# AD9364_Interface.net
KiCad netlist of a schematic drawn in Altium Designer
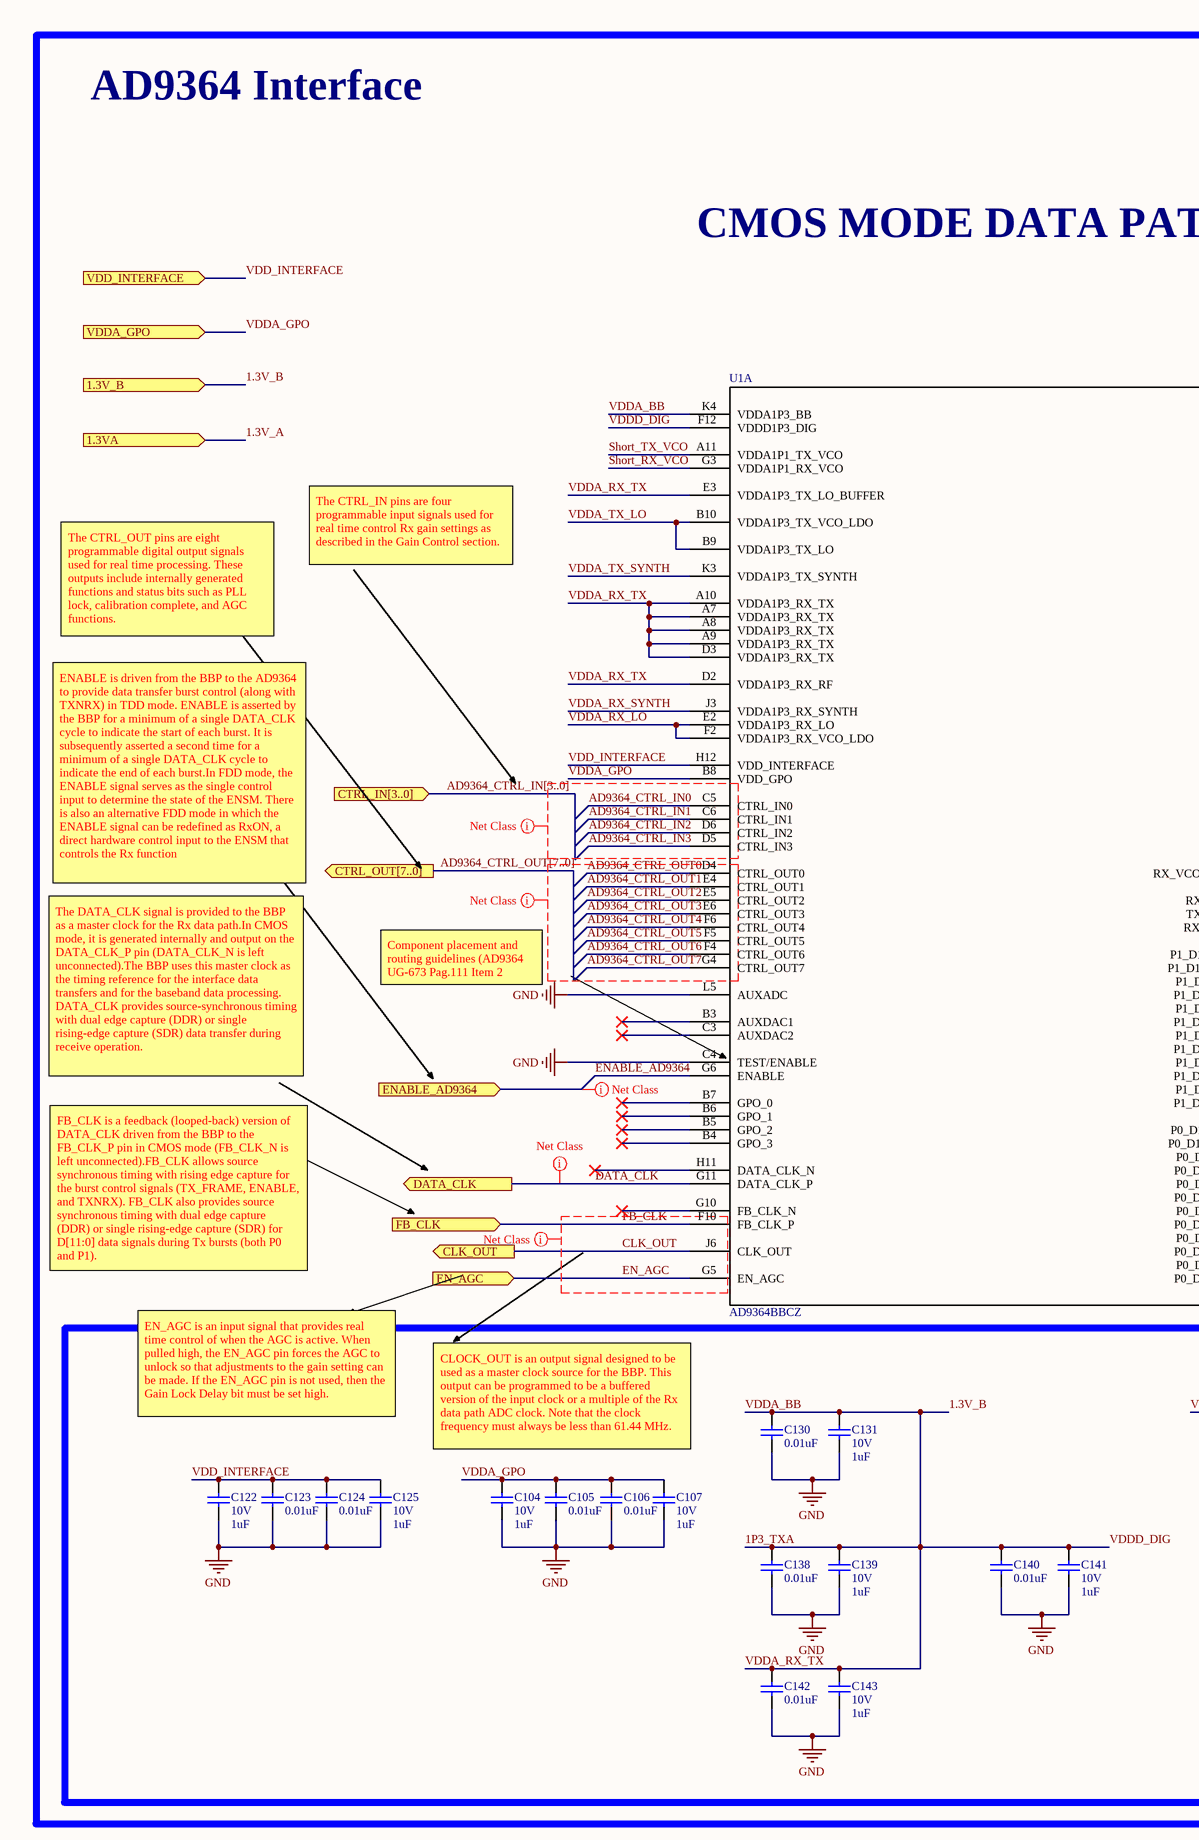
[diagram p0: AD9364_Interface.SchDoc, left]
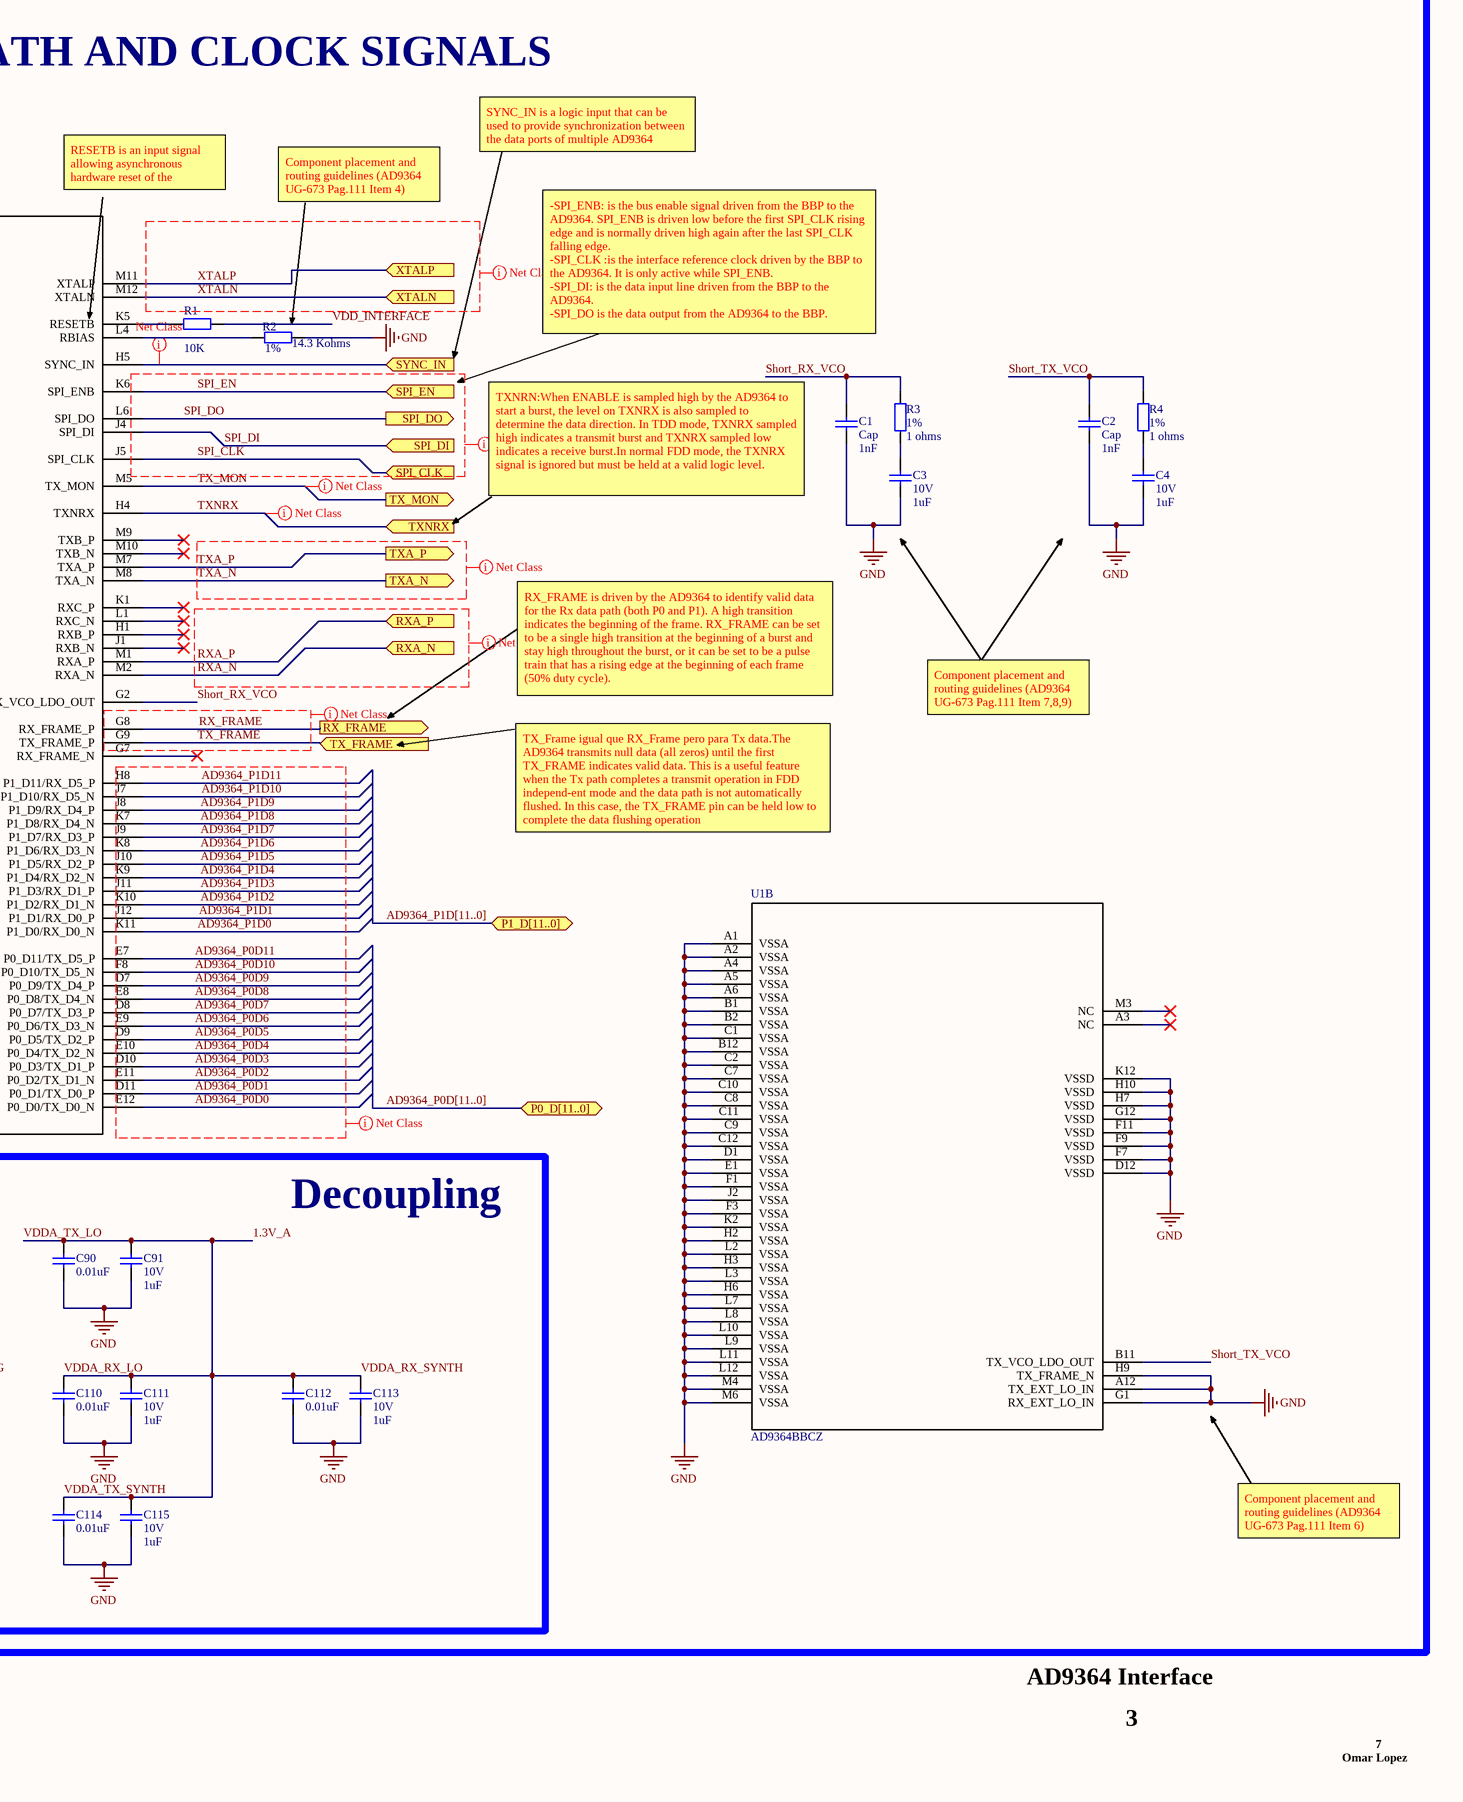
[diagram p1: AD9364_Interface.SchDoc, right]

(export (version "E")
  (design (tool "Eeschema 10.0.6"))
  (components
    (comp (ref "C1")
      (value "Cap")
      (footprint "MurataCapacitor:GRM0402MurataCap")
      (description "Capacitor")
      (fields
        (field (name "ALTIUM_VALUE") "1nF")
        (field (name "MANUFACTURER") "Murata")
        (field (name "TOLERANCE") "10%")
      )
      (libsource (lib "Miscellaneous Devices") (part "Cap"))
    )
    (comp (ref "C2")
      (value "Cap")
      (footprint "MurataCapacitor:GRM0402MurataCap")
      (description "Capacitor")
      (fields
        (field (name "ALTIUM_VALUE") "1nF")
        (field (name "MANUFACTURER") "Murata")
        (field (name "TOLERANCE") "10%")
      )
      (libsource (lib "Miscellaneous Devices") (part "Cap"))
    )
    (comp (ref "C3")
      (value "10V")
      (footprint "MurataCapacitor:GRM0402MurataCap")
      (description "Capacitor")
      (fields
        (field (name "ALTIUM_VALUE") "1uF")
        (field (name "MANUFACTURER") "Murata")
        (field (name "TOLERANCE") "10%")
      )
      (libsource (lib "Miscellaneous Devices") (part "Cap"))
    )
    (comp (ref "C4")
      (value "10V")
      (footprint "MurataCapacitor:GRM0402MurataCap")
      (description "Capacitor")
      (fields
        (field (name "ALTIUM_VALUE") "1uF")
        (field (name "MANUFACTURER") "Murata")
        (field (name "TOLERANCE") "10%")
      )
      (libsource (lib "Miscellaneous Devices") (part "Cap"))
    )
    (comp (ref "C90")
      (value "0.01uF")
      (footprint "MurataCapacitor:GRM0402MurataCap")
      (description "Capacitor")
      (fields (field (name "MANUFACTURER") "Murata") (field (name "TOLERANCE") "10%"))
      (libsource (lib "Miscellaneous Devices") (part "Cap"))
    )
    (comp (ref "C91")
      (value "10V")
      (footprint "MurataCapacitor:GRM0402MurataCap")
      (description "Capacitor")
      (fields
        (field (name "ALTIUM_VALUE") "1uF")
        (field (name "MANUFACTURER") "Murata")
        (field (name "TOLERANCE") "10%")
      )
      (libsource (lib "Miscellaneous Devices") (part "Cap"))
    )
    (comp (ref "C104")
      (value "10V")
      (footprint "MurataCapacitor:GRM0402MurataCap")
      (description "Capacitor")
      (fields
        (field (name "ALTIUM_VALUE") "1uF")
        (field (name "MANUFACTURER") "Murata")
        (field (name "TOLERANCE") "10%")
      )
      (libsource (lib "Miscellaneous Devices") (part "Cap"))
    )
    (comp (ref "C105")
      (value "0.01uF")
      (footprint "MurataCapacitor:GRM0402MurataCap")
      (description "Capacitor")
      (fields (field (name "MANUFACTURER") "Murata") (field (name "TOLERANCE") "10%"))
      (libsource (lib "Miscellaneous Devices") (part "Cap"))
    )
    (comp (ref "C106")
      (value "0.01uF")
      (footprint "MurataCapacitor:GRM0402MurataCap")
      (description "Capacitor")
      (fields (field (name "MANUFACTURER") "Murata") (field (name "TOLERANCE") "10%"))
      (libsource (lib "Miscellaneous Devices") (part "Cap"))
    )
    (comp (ref "C107")
      (value "10V")
      (footprint "MurataCapacitor:GRM0402MurataCap")
      (description "Capacitor")
      (fields
        (field (name "ALTIUM_VALUE") "1uF")
        (field (name "MANUFACTURER") "Murata")
        (field (name "TOLERANCE") "10%")
      )
      (libsource (lib "Miscellaneous Devices") (part "Cap"))
    )
    (comp (ref "C110")
      (value "0.01uF")
      (footprint "MurataCapacitor:GRM0402MurataCap")
      (description "Capacitor")
      (fields (field (name "MANUFACTURER") "Murata") (field (name "TOLERANCE") "10%"))
      (libsource (lib "Miscellaneous Devices") (part "Cap"))
    )
    (comp (ref "C111")
      (value "10V")
      (footprint "MurataCapacitor:GRM0402MurataCap")
      (description "Capacitor")
      (fields
        (field (name "ALTIUM_VALUE") "1uF")
        (field (name "MANUFACTURER") "Murata")
        (field (name "TOLERANCE") "10%")
      )
      (libsource (lib "Miscellaneous Devices") (part "Cap"))
    )
    (comp (ref "C112")
      (value "0.01uF")
      (footprint "MurataCapacitor:GRM0402MurataCap")
      (description "Capacitor")
      (fields (field (name "MANUFACTURER") "Murata") (field (name "TOLERANCE") "10%"))
      (libsource (lib "Miscellaneous Devices") (part "Cap"))
    )
    (comp (ref "C113")
      (value "10V")
      (footprint "MurataCapacitor:GRM0402MurataCap")
      (description "Capacitor")
      (fields
        (field (name "ALTIUM_VALUE") "1uF")
        (field (name "MANUFACTURER") "Murata")
        (field (name "TOLERANCE") "10%")
      )
      (libsource (lib "Miscellaneous Devices") (part "Cap"))
    )
    (comp (ref "C114")
      (value "0.01uF")
      (footprint "MurataCapacitor:GRM0402MurataCap")
      (description "Capacitor")
      (fields (field (name "MANUFACTURER") "Murata") (field (name "TOLERANCE") "10%"))
      (libsource (lib "Miscellaneous Devices") (part "Cap"))
    )
    (comp (ref "C115")
      (value "10V")
      (footprint "MurataCapacitor:GRM0402MurataCap")
      (description "Capacitor")
      (fields
        (field (name "ALTIUM_VALUE") "1uF")
        (field (name "MANUFACTURER") "Murata")
        (field (name "TOLERANCE") "10%")
      )
      (libsource (lib "Miscellaneous Devices") (part "Cap"))
    )
    (comp (ref "C122")
      (value "10V")
      (footprint "MurataCapacitor:GRM0402MurataCap")
      (description "Capacitor")
      (fields
        (field (name "ALTIUM_VALUE") "1uF")
        (field (name "MANUFACTURER") "Murata")
        (field (name "TOLERANCE") "10%")
      )
      (libsource (lib "Miscellaneous Devices") (part "Cap"))
    )
    (comp (ref "C123")
      (value "0.01uF")
      (footprint "MurataCapacitor:GRM0402MurataCap")
      (description "Capacitor")
      (fields (field (name "MANUFACTURER") "Murata") (field (name "TOLERANCE") "10%"))
      (libsource (lib "Miscellaneous Devices") (part "Cap"))
    )
    (comp (ref "C124")
      (value "0.01uF")
      (footprint "MurataCapacitor:GRM0402MurataCap")
      (description "Capacitor")
      (fields (field (name "MANUFACTURER") "Murata") (field (name "TOLERANCE") "10%"))
      (libsource (lib "Miscellaneous Devices") (part "Cap"))
    )
    (comp (ref "C125")
      (value "10V")
      (footprint "MurataCapacitor:GRM0402MurataCap")
      (description "Capacitor")
      (fields
        (field (name "ALTIUM_VALUE") "1uF")
        (field (name "MANUFACTURER") "Murata")
        (field (name "TOLERANCE") "10%")
      )
      (libsource (lib "Miscellaneous Devices") (part "Cap"))
    )
    (comp (ref "C130")
      (value "0.01uF")
      (footprint "MurataCapacitor:GRM0402MurataCap")
      (description "Capacitor")
      (fields (field (name "MANUFACTURER") "Murata") (field (name "TOLERANCE") "10%"))
      (libsource (lib "Miscellaneous Devices") (part "Cap"))
    )
    (comp (ref "C131")
      (value "10V")
      (footprint "MurataCapacitor:GRM0402MurataCap")
      (description "Capacitor")
      (fields
        (field (name "ALTIUM_VALUE") "1uF")
        (field (name "MANUFACTURER") "Murata")
        (field (name "TOLERANCE") "10%")
      )
      (libsource (lib "Miscellaneous Devices") (part "Cap"))
    )
    (comp (ref "C138")
      (value "0.01uF")
      (footprint "MurataCapacitor:GRM0402MurataCap")
      (description "Capacitor")
      (fields (field (name "MANUFACTURER") "Murata") (field (name "TOLERANCE") "10%"))
      (libsource (lib "Miscellaneous Devices") (part "Cap"))
    )
    (comp (ref "C139")
      (value "10V")
      (footprint "MurataCapacitor:GRM0402MurataCap")
      (description "Capacitor")
      (fields
        (field (name "ALTIUM_VALUE") "1uF")
        (field (name "MANUFACTURER") "Murata")
        (field (name "TOLERANCE") "10%")
      )
      (libsource (lib "Miscellaneous Devices") (part "Cap"))
    )
    (comp (ref "C140")
      (value "0.01uF")
      (footprint "MurataCapacitor:GRM0402MurataCap")
      (description "Capacitor")
      (fields (field (name "MANUFACTURER") "Murata") (field (name "TOLERANCE") "10%"))
      (libsource (lib "Miscellaneous Devices") (part "Cap"))
    )
    (comp (ref "C141")
      (value "10V")
      (footprint "MurataCapacitor:GRM0402MurataCap")
      (description "Capacitor")
      (fields
        (field (name "ALTIUM_VALUE") "1uF")
        (field (name "MANUFACTURER") "Murata")
        (field (name "TOLERANCE") "10%")
      )
      (libsource (lib "Miscellaneous Devices") (part "Cap"))
    )
    (comp (ref "C142")
      (value "0.01uF")
      (footprint "MurataCapacitor:GRM0402MurataCap")
      (description "Capacitor")
      (fields (field (name "MANUFACTURER") "Murata") (field (name "TOLERANCE") "10%"))
      (libsource (lib "Miscellaneous Devices") (part "Cap"))
    )
    (comp (ref "C143")
      (value "10V")
      (footprint "MurataCapacitor:GRM0402MurataCap")
      (description "Capacitor")
      (fields
        (field (name "ALTIUM_VALUE") "1uF")
        (field (name "MANUFACTURER") "Murata")
        (field (name "TOLERANCE") "10%")
      )
      (libsource (lib "Miscellaneous Devices") (part "Cap"))
    )
    (comp (ref "R1")
      (value "10K")
      (footprint "Res0402ERJ:RC0402N")
      (description "Resistor")
      (fields (field (name "MANUFACTURER") "Panasonic") (field (name "TOLERANCE") "1%"))
      (libsource (lib "Miscellaneous Devices") (part "Res2"))
    )
    (comp (ref "R2")
      (value "1%")
      (footprint "Res0402ERJ:RC0402N")
      (description "Resistor")
      (fields
        (field (name "ALTIUM_VALUE") "14.3 Kohms")
        (field (name "MANUFACTURER") "Panasonic")
        (field (name "PARTNUMBER") "ERJ-2RKF1432X")
      )
      (libsource (lib "Miscellaneous Devices") (part "Res2"))
    )
    (comp (ref "R3")
      (value "1%")
      (footprint "RC0402N")
      (description "Resistor")
      (fields
        (field (name "ALTIUM_VALUE") "1 ohms")
        (field (name "MANUFACTURER") "Panasonic")
        (field (name "TOLERANCE") "5%")
      )
      (libsource (lib "") (part "Res2_1"))
    )
    (comp (ref "R4")
      (value "1%")
      (footprint "RC0402N")
      (description "Resistor")
      (fields
        (field (name "ALTIUM_VALUE") "1 ohms")
        (field (name "MANUFACTURER") "Panasonic")
        (field (name "TOLERANCE") "5%")
      )
      (libsource (lib "") (part "Res2_1"))
    )
    (comp (ref "U1")
      (value "AD9364BBCZ")
      (footprint "AD9364:BC_144_7_")
      (description "Transceiver")
      (fields (field (name "MANUFACTURER") "Analog Devices"))
      (libsource (lib "AD9364") (part "AD9364BBCZ"))
    )
  )
  (nets
    (net (code "1") (name "/1.3V_A") (class "Default")
      (node (ref "C110") (pin "2") (pinfunction "2_2") (pintype "passive"))
      (node (ref "C111") (pin "2") (pinfunction "2_2") (pintype "passive"))
      (node (ref "C112") (pin "2") (pinfunction "2_2") (pintype "passive"))
      (node (ref "C113") (pin "2") (pinfunction "2_2") (pintype "passive"))
      (node (ref "C114") (pin "2") (pinfunction "2_2") (pintype "passive"))
      (node (ref "C115") (pin "2") (pinfunction "2_2") (pintype "passive"))
      (node (ref "C90") (pin "2") (pinfunction "2_2") (pintype "passive"))
      (node (ref "C91") (pin "2") (pinfunction "2_2") (pintype "passive"))
      (node (ref "U1") (pin "B10") (pinfunction "VDDA1P3_TX_VCO_LDO_B10") (pintype "passive"))
      (node (ref "U1") (pin "B9") (pinfunction "VDDA1P3_TX_LO_B9") (pintype "passive"))
      (node (ref "U1") (pin "E2") (pinfunction "VDDA1P3_RX_LO_E2") (pintype "passive"))
      (node (ref "U1") (pin "F2") (pinfunction "VDDA1P3_RX_VCO_LDO_F2") (pintype "passive"))
      (node (ref "U1") (pin "J3") (pinfunction "VDDA1P3_RX_SYNTH_J3") (pintype "passive"))
      (node (ref "U1") (pin "K3") (pinfunction "VDDA1P3_TX_SYNTH_K3") (pintype "passive"))
    )
    (net (code "2") (name "/1.3V_B") (class "Default")
      (node (ref "C130") (pin "2") (pinfunction "2_2") (pintype "passive"))
      (node (ref "C131") (pin "2") (pinfunction "2_2") (pintype "passive"))
      (node (ref "C138") (pin "2") (pinfunction "2_2") (pintype "passive"))
      (node (ref "C139") (pin "2") (pinfunction "2_2") (pintype "passive"))
      (node (ref "C140") (pin "2") (pinfunction "2_2") (pintype "passive"))
      (node (ref "C141") (pin "2") (pinfunction "2_2") (pintype "passive"))
      (node (ref "C142") (pin "2") (pinfunction "2_2") (pintype "passive"))
      (node (ref "C143") (pin "2") (pinfunction "2_2") (pintype "passive"))
      (node (ref "U1") (pin "A10") (pinfunction "VDDA1P3_RX_TX_A10") (pintype "passive"))
      (node (ref "U1") (pin "A7") (pinfunction "VDDA1P3_RX_TX_A7") (pintype "passive"))
      (node (ref "U1") (pin "A8") (pinfunction "VDDA1P3_RX_TX_A8") (pintype "passive"))
      (node (ref "U1") (pin "A9") (pinfunction "VDDA1P3_RX_TX_A9") (pintype "passive"))
      (node (ref "U1") (pin "D2") (pinfunction "VDDA1P3_RX_RF_D2") (pintype "passive"))
      (node (ref "U1") (pin "D3") (pinfunction "VDDA1P3_RX_TX_D3") (pintype "passive"))
      (node (ref "U1") (pin "E3") (pinfunction "VDDA1P3_TX_LO_BUFFER_E3") (pintype "passive"))
      (node (ref "U1") (pin "F12") (pinfunction "VDDD1P3_DIG_F12") (pintype "passive"))
      (node (ref "U1") (pin "K4") (pinfunction "VDDA1P3_BB_K4") (pintype "passive"))
    )
    (net (code "3") (name "/AD9364_CTRL_IN0") (class "Default")
      (node (ref "U1") (pin "C5") (pinfunction "CTRL_IN0_C5") (pintype "passive"))
    )
    (net (code "4") (name "/AD9364_CTRL_IN1") (class "Default")
      (node (ref "U1") (pin "C6") (pinfunction "CTRL_IN1_C6") (pintype "passive"))
    )
    (net (code "5") (name "/AD9364_CTRL_IN2") (class "Default")
      (node (ref "U1") (pin "D6") (pinfunction "CTRL_IN2_D6") (pintype "passive"))
    )
    (net (code "6") (name "/AD9364_CTRL_IN3") (class "Default")
      (node (ref "U1") (pin "D5") (pinfunction "CTRL_IN3_D5") (pintype "passive"))
    )
    (net (code "8") (name "/AD9364_CTRL_OUT0") (class "Default")
      (node (ref "U1") (pin "D4") (pinfunction "CTRL_OUT0_D4") (pintype "passive"))
    )
    (net (code "9") (name "/AD9364_CTRL_OUT1") (class "Default")
      (node (ref "U1") (pin "E4") (pinfunction "CTRL_OUT1_E4") (pintype "passive"))
    )
    (net (code "10") (name "/AD9364_CTRL_OUT2") (class "Default")
      (node (ref "U1") (pin "E5") (pinfunction "CTRL_OUT2_E5") (pintype "passive"))
    )
    (net (code "11") (name "/AD9364_CTRL_OUT3") (class "Default")
      (node (ref "U1") (pin "E6") (pinfunction "CTRL_OUT3_E6") (pintype "passive"))
    )
    (net (code "12") (name "/AD9364_CTRL_OUT4") (class "Default")
      (node (ref "U1") (pin "F6") (pinfunction "CTRL_OUT4_F6") (pintype "passive"))
    )
    (net (code "13") (name "/AD9364_CTRL_OUT5") (class "Default")
      (node (ref "U1") (pin "F5") (pinfunction "CTRL_OUT5_F5") (pintype "passive"))
    )
    (net (code "14") (name "/AD9364_CTRL_OUT6") (class "Default")
      (node (ref "U1") (pin "F4") (pinfunction "CTRL_OUT6_F4") (pintype "passive"))
    )
    (net (code "15") (name "/AD9364_CTRL_OUT7") (class "Default")
      (node (ref "U1") (pin "G4") (pinfunction "CTRL_OUT7_G4") (pintype "passive"))
    )
    (net (code "17") (name "/AD9364_P0D0") (class "Default")
      (node (ref "U1") (pin "E12") (pinfunction "P0_D0/TX_D0_N_E12") (pintype "passive"))
    )
    (net (code "18") (name "/AD9364_P0D1") (class "Default")
      (node (ref "U1") (pin "D11") (pinfunction "P0_D1/TX_D0_P_D11") (pintype "passive"))
    )
    (net (code "19") (name "/AD9364_P0D2") (class "Default")
      (node (ref "U1") (pin "E11") (pinfunction "P0_D2/TX_D1_N_E11") (pintype "passive"))
    )
    (net (code "20") (name "/AD9364_P0D3") (class "Default")
      (node (ref "U1") (pin "D10") (pinfunction "P0_D3/TX_D1_P_D10") (pintype "passive"))
    )
    (net (code "21") (name "/AD9364_P0D4") (class "Default")
      (node (ref "U1") (pin "E10") (pinfunction "P0_D4/TX_D2_N_E10") (pintype "passive"))
    )
    (net (code "22") (name "/AD9364_P0D5") (class "Default")
      (node (ref "U1") (pin "D9") (pinfunction "P0_D5/TX_D2_P_D9") (pintype "passive"))
    )
    (net (code "23") (name "/AD9364_P0D6") (class "Default")
      (node (ref "U1") (pin "E9") (pinfunction "P0_D6/TX_D3_N_E9") (pintype "passive"))
    )
    (net (code "24") (name "/AD9364_P0D7") (class "Default")
      (node (ref "U1") (pin "D8") (pinfunction "P0_D7/TX_D3_P_D8") (pintype "passive"))
    )
    (net (code "25") (name "/AD9364_P0D8") (class "Default")
      (node (ref "U1") (pin "E8") (pinfunction "P0_D8/TX_D4_N_E8") (pintype "passive"))
    )
    (net (code "26") (name "/AD9364_P0D9") (class "Default")
      (node (ref "U1") (pin "D7") (pinfunction "P0_D9/TX_D4_P_D7") (pintype "passive"))
    )
    (net (code "27") (name "/AD9364_P0D10") (class "Default")
      (node (ref "U1") (pin "F8") (pinfunction "P0_D10/TX_D5_N_F8") (pintype "passive"))
    )
    (net (code "28") (name "/AD9364_P0D11") (class "Default")
      (node (ref "U1") (pin "E7") (pinfunction "P0_D11/TX_D5_P_E7") (pintype "passive"))
    )
    (net (code "30") (name "/AD9364_P1D0") (class "Default")
      (node (ref "U1") (pin "K11") (pinfunction "P1_D0/RX_D0_N_K11") (pintype "passive"))
    )
    (net (code "31") (name "/AD9364_P1D1") (class "Default")
      (node (ref "U1") (pin "J12") (pinfunction "P1_D1/RX_D0_P_J12") (pintype "passive"))
    )
    (net (code "32") (name "/AD9364_P1D2") (class "Default")
      (node (ref "U1") (pin "K10") (pinfunction "P1_D2/RX_D1_N_K10") (pintype "passive"))
    )
    (net (code "33") (name "/AD9364_P1D3") (class "Default")
      (node (ref "U1") (pin "J11") (pinfunction "P1_D3/RX_D1_P_J11") (pintype "passive"))
    )
    (net (code "34") (name "/AD9364_P1D4") (class "Default")
      (node (ref "U1") (pin "K9") (pinfunction "P1_D4/RX_D2_N_K9") (pintype "passive"))
    )
    (net (code "35") (name "/AD9364_P1D5") (class "Default")
      (node (ref "U1") (pin "J10") (pinfunction "P1_D5/RX_D2_P_J10") (pintype "passive"))
    )
    (net (code "36") (name "/AD9364_P1D6") (class "Default")
      (node (ref "U1") (pin "K8") (pinfunction "P1_D6/RX_D3_N_K8") (pintype "passive"))
    )
    (net (code "37") (name "/AD9364_P1D7") (class "Default")
      (node (ref "U1") (pin "J9") (pinfunction "P1_D7/RX_D3_P_J9") (pintype "passive"))
    )
    (net (code "38") (name "/AD9364_P1D8") (class "Default")
      (node (ref "U1") (pin "K7") (pinfunction "P1_D8/RX_D4_N_K7") (pintype "passive"))
    )
    (net (code "39") (name "/AD9364_P1D9") (class "Default")
      (node (ref "U1") (pin "J8") (pinfunction "P1_D9/RX_D4_P_J8") (pintype "passive"))
    )
    (net (code "40") (name "/AD9364_P1D10") (class "Default")
      (node (ref "U1") (pin "J7") (pinfunction "P1_D10/RX_D5_N_J7") (pintype "passive"))
    )
    (net (code "41") (name "/AD9364_P1D11") (class "Default")
      (node (ref "U1") (pin "H8") (pinfunction "P1_D11/RX_D5_P_H8") (pintype "passive"))
    )
    (net (code "43") (name "/CLK_OUT") (class "Default")
      (node (ref "U1") (pin "J6") (pinfunction "CLK_OUT_J6") (pintype "passive"))
    )
    (net (code "44") (name "/DATA_CLK") (class "Default")
      (node (ref "U1") (pin "G11") (pinfunction "DATA_CLK_P_G11") (pintype "passive"))
    )
    (net (code "45") (name "/ENABLE_AD9364") (class "Default")
      (node (ref "U1") (pin "G6") (pinfunction "ENABLE_G6") (pintype "passive"))
    )
    (net (code "46") (name "/EN_AGC") (class "Default")
      (node (ref "U1") (pin "G5") (pinfunction "EN_AGC_G5") (pintype "passive"))
    )
    (net (code "47") (name "/FB_CLK") (class "Default")
      (node (ref "U1") (pin "F10") (pinfunction "FB_CLK_P_F10") (pintype "passive"))
    )
    (net (code "48") (name "/RXA_N") (class "Default")
      (node (ref "U1") (pin "M2") (pinfunction "RXA_N_M2") (pintype "passive"))
    )
    (net (code "49") (name "/RXA_P") (class "Default")
      (node (ref "U1") (pin "M1") (pinfunction "RXA_P_M1") (pintype "passive"))
    )
    (net (code "50") (name "/RX_FRAME") (class "Default")
      (node (ref "U1") (pin "G8") (pinfunction "RX_FRAME_P_G8") (pintype "passive"))
    )
    (net (code "51") (name "/SPI_CLK") (class "Default")
      (node (ref "U1") (pin "J5") (pinfunction "SPI_CLK_J5") (pintype "passive"))
    )
    (net (code "52") (name "/SPI_DI") (class "Default")
      (node (ref "U1") (pin "J4") (pinfunction "SPI_DI_J4") (pintype "passive"))
    )
    (net (code "53") (name "/SPI_DO") (class "Default")
      (node (ref "U1") (pin "L6") (pinfunction "SPI_DO_L6") (pintype "passive"))
    )
    (net (code "54") (name "/SPI_EN") (class "Default")
      (node (ref "U1") (pin "K6") (pinfunction "SPI_ENB_K6") (pintype "passive"))
    )
    (net (code "55") (name "/SYNC_IN") (class "Default")
      (node (ref "U1") (pin "H5") (pinfunction "SYNC_IN_H5") (pintype "passive"))
    )
    (net (code "56") (name "/Short_RX_VCO") (class "Default")
      (node (ref "C1") (pin "1") (pinfunction "1_1") (pintype "passive"))
      (node (ref "R3") (pin "1") (pinfunction "1_1") (pintype "passive"))
      (node (ref "U1") (pin "G2") (pinfunction "RX_VCO_LDO_OUT_G2") (pintype "passive"))
      (node (ref "U1") (pin "G3") (pinfunction "VDDA1P1_RX_VCO_G3") (pintype "passive"))
    )
    (net (code "57") (name "/Short_TX_VCO") (class "Default")
      (node (ref "C2") (pin "1") (pinfunction "1_1") (pintype "passive"))
      (node (ref "R4") (pin "1") (pinfunction "1_1") (pintype "passive"))
      (node (ref "U1") (pin "A11") (pinfunction "VDDA1P1_TX_VCO_A11") (pintype "passive"))
      (node (ref "U1") (pin "B11") (pinfunction "TX_VCO_LDO_OUT_B11") (pintype "passive"))
    )
    (net (code "58") (name "/TXA_N") (class "Default")
      (node (ref "U1") (pin "M8") (pinfunction "TXA_N_M8") (pintype "passive"))
    )
    (net (code "59") (name "/TXA_P") (class "Default")
      (node (ref "U1") (pin "M7") (pinfunction "TXA_P_M7") (pintype "passive"))
    )
    (net (code "60") (name "/TXNRX") (class "Default")
      (node (ref "U1") (pin "H4") (pinfunction "TXNRX_H4") (pintype "passive"))
    )
    (net (code "61") (name "/TX_FRAME") (class "Default")
      (node (ref "U1") (pin "G9") (pinfunction "TX_FRAME_P_G9") (pintype "passive"))
    )
    (net (code "62") (name "/TX_MON") (class "Default")
      (node (ref "U1") (pin "M5") (pinfunction "TX_MON_M5") (pintype "passive"))
    )
    (net (code "63") (name "/VDDA_GPO") (class "Default")
      (node (ref "C104") (pin "2") (pinfunction "2_2") (pintype "passive"))
      (node (ref "C105") (pin "2") (pinfunction "2_2") (pintype "passive"))
      (node (ref "C106") (pin "2") (pinfunction "2_2") (pintype "passive"))
      (node (ref "C107") (pin "2") (pinfunction "2_2") (pintype "passive"))
      (node (ref "U1") (pin "B8") (pinfunction "VDD_GPO_B8") (pintype "passive"))
    )
    (net (code "64") (name "/VDD_INTERFACE") (class "Default")
      (node (ref "C122") (pin "2") (pinfunction "2_2") (pintype "passive"))
      (node (ref "C123") (pin "2") (pinfunction "2_2") (pintype "passive"))
      (node (ref "C124") (pin "2") (pinfunction "2_2") (pintype "passive"))
      (node (ref "C125") (pin "2") (pinfunction "2_2") (pintype "passive"))
      (node (ref "R1") (pin "1") (pinfunction "1_1") (pintype "passive"))
      (node (ref "U1") (pin "H12") (pinfunction "VDD_INTERFACE_H12") (pintype "passive"))
    )
    (net (code "65") (name "/XTALN") (class "Default")
      (node (ref "U1") (pin "M12") (pinfunction "XTALN_M12") (pintype "passive"))
    )
    (net (code "66") (name "/XTALP") (class "Default")
      (node (ref "U1") (pin "M11") (pinfunction "XTALP_M11") (pintype "passive"))
    )
    (net (code "67") (name "GND") (class "Default")
      (node (ref "C1") (pin "2") (pinfunction "2_2") (pintype "passive"))
      (node (ref "C104") (pin "1") (pinfunction "1_1") (pintype "passive"))
      (node (ref "C105") (pin "1") (pinfunction "1_1") (pintype "passive"))
      (node (ref "C106") (pin "1") (pinfunction "1_1") (pintype "passive"))
      (node (ref "C107") (pin "1") (pinfunction "1_1") (pintype "passive"))
      (node (ref "C110") (pin "1") (pinfunction "1_1") (pintype "passive"))
      (node (ref "C111") (pin "1") (pinfunction "1_1") (pintype "passive"))
      (node (ref "C112") (pin "1") (pinfunction "1_1") (pintype "passive"))
      (node (ref "C113") (pin "1") (pinfunction "1_1") (pintype "passive"))
      (node (ref "C114") (pin "1") (pinfunction "1_1") (pintype "passive"))
      (node (ref "C115") (pin "1") (pinfunction "1_1") (pintype "passive"))
      (node (ref "C122") (pin "1") (pinfunction "1_1") (pintype "passive"))
      (node (ref "C123") (pin "1") (pinfunction "1_1") (pintype "passive"))
      (node (ref "C124") (pin "1") (pinfunction "1_1") (pintype "passive"))
      (node (ref "C125") (pin "1") (pinfunction "1_1") (pintype "passive"))
      (node (ref "C130") (pin "1") (pinfunction "1_1") (pintype "passive"))
      (node (ref "C131") (pin "1") (pinfunction "1_1") (pintype "passive"))
      (node (ref "C138") (pin "1") (pinfunction "1_1") (pintype "passive"))
      (node (ref "C139") (pin "1") (pinfunction "1_1") (pintype "passive"))
      (node (ref "C140") (pin "1") (pinfunction "1_1") (pintype "passive"))
      (node (ref "C141") (pin "1") (pinfunction "1_1") (pintype "passive"))
      (node (ref "C142") (pin "1") (pinfunction "1_1") (pintype "passive"))
      (node (ref "C143") (pin "1") (pinfunction "1_1") (pintype "passive"))
      (node (ref "C2") (pin "2") (pinfunction "2_2") (pintype "passive"))
      (node (ref "C3") (pin "2") (pinfunction "2_2") (pintype "passive"))
      (node (ref "C4") (pin "2") (pinfunction "2_2") (pintype "passive"))
      (node (ref "C90") (pin "1") (pinfunction "1_1") (pintype "passive"))
      (node (ref "C91") (pin "1") (pinfunction "1_1") (pintype "passive"))
      (node (ref "R2") (pin "1") (pinfunction "1_1") (pintype "passive"))
      (node (ref "U1") (pin "A1") (pinfunction "VSSA_A1") (pintype "passive"))
      (node (ref "U1") (pin "A12") (pinfunction "TX_EXT_LO_IN_A12") (pintype "passive"))
      (node (ref "U1") (pin "A2") (pinfunction "VSSA_A2") (pintype "passive"))
      (node (ref "U1") (pin "A4") (pinfunction "VSSA_A4") (pintype "passive"))
      (node (ref "U1") (pin "A5") (pinfunction "VSSA_A5") (pintype "passive"))
      (node (ref "U1") (pin "A6") (pinfunction "VSSA_A6") (pintype "passive"))
      (node (ref "U1") (pin "B1") (pinfunction "VSSA_B1") (pintype "passive"))
      (node (ref "U1") (pin "B12") (pinfunction "VSSA_B12") (pintype "passive"))
      (node (ref "U1") (pin "B2") (pinfunction "VSSA_B2") (pintype "passive"))
      (node (ref "U1") (pin "C1") (pinfunction "VSSA_C1") (pintype "passive"))
      (node (ref "U1") (pin "C10") (pinfunction "VSSA_C10") (pintype "passive"))
      (node (ref "U1") (pin "C11") (pinfunction "VSSA_C11") (pintype "passive"))
      (node (ref "U1") (pin "C12") (pinfunction "VSSA_C12") (pintype "passive"))
      (node (ref "U1") (pin "C2") (pinfunction "VSSA_C2") (pintype "passive"))
      (node (ref "U1") (pin "C4") (pinfunction "TEST/ENABLE_C4") (pintype "passive"))
      (node (ref "U1") (pin "C7") (pinfunction "VSSA_C7") (pintype "passive"))
      (node (ref "U1") (pin "C8") (pinfunction "VSSA_C8") (pintype "passive"))
      (node (ref "U1") (pin "C9") (pinfunction "VSSA_C9") (pintype "passive"))
      (node (ref "U1") (pin "D1") (pinfunction "VSSA_D1") (pintype "passive"))
      (node (ref "U1") (pin "D12") (pinfunction "VSSD_D12") (pintype "passive"))
      (node (ref "U1") (pin "E1") (pinfunction "VSSA_E1") (pintype "passive"))
      (node (ref "U1") (pin "F1") (pinfunction "VSSA_F1") (pintype "passive"))
      (node (ref "U1") (pin "F11") (pinfunction "VSSD_F11") (pintype "passive"))
      (node (ref "U1") (pin "F3") (pinfunction "VSSA_F3") (pintype "passive"))
      (node (ref "U1") (pin "F7") (pinfunction "VSSD_F7") (pintype "passive"))
      (node (ref "U1") (pin "F9") (pinfunction "VSSD_F9") (pintype "passive"))
      (node (ref "U1") (pin "G1") (pinfunction "RX_EXT_LO_IN_G1") (pintype "passive"))
      (node (ref "U1") (pin "G12") (pinfunction "VSSD_G12") (pintype "passive"))
      (node (ref "U1") (pin "H10") (pinfunction "VSSD_H10") (pintype "passive"))
      (node (ref "U1") (pin "H2") (pinfunction "VSSA_H2") (pintype "passive"))
      (node (ref "U1") (pin "H3") (pinfunction "VSSA_H3") (pintype "passive"))
      (node (ref "U1") (pin "H6") (pinfunction "VSSA_H6") (pintype "passive"))
      (node (ref "U1") (pin "H7") (pinfunction "VSSD_H7") (pintype "passive"))
      (node (ref "U1") (pin "H9") (pinfunction "TX_FRAME_N_H9") (pintype "passive"))
      (node (ref "U1") (pin "J2") (pinfunction "VSSA_J2") (pintype "passive"))
      (node (ref "U1") (pin "K12") (pinfunction "VSSD_K12") (pintype "passive"))
      (node (ref "U1") (pin "K2") (pinfunction "VSSA_K2") (pintype "passive"))
      (node (ref "U1") (pin "L10") (pinfunction "VSSA_L10") (pintype "passive"))
      (node (ref "U1") (pin "L11") (pinfunction "VSSA_L11") (pintype "passive"))
      (node (ref "U1") (pin "L12") (pinfunction "VSSA_L12") (pintype "passive"))
      (node (ref "U1") (pin "L2") (pinfunction "VSSA_L2") (pintype "passive"))
      (node (ref "U1") (pin "L3") (pinfunction "VSSA_L3") (pintype "passive"))
      (node (ref "U1") (pin "L5") (pinfunction "AUXADC_L5") (pintype "passive"))
      (node (ref "U1") (pin "L7") (pinfunction "VSSA_L7") (pintype "passive"))
      (node (ref "U1") (pin "L8") (pinfunction "VSSA_L8") (pintype "passive"))
      (node (ref "U1") (pin "L9") (pinfunction "VSSA_L9") (pintype "passive"))
      (node (ref "U1") (pin "M4") (pinfunction "VSSA_M4") (pintype "passive"))
      (node (ref "U1") (pin "M6") (pinfunction "VSSA_M6") (pintype "passive"))
    )
    (net (code "68") (name "Net-(C3-Pad1)") (class "Default")
      (node (ref "C3") (pin "1") (pinfunction "1_1") (pintype "passive"))
      (node (ref "R3") (pin "2") (pinfunction "2_2") (pintype "passive"))
    )
    (net (code "69") (name "Net-(C4-Pad1)") (class "Default")
      (node (ref "C4") (pin "1") (pinfunction "1_1") (pintype "passive"))
      (node (ref "R4") (pin "2") (pinfunction "2_2") (pintype "passive"))
    )
    (net (code "70") (name "Net-(U1A-RBIAS)") (class "Default")
      (node (ref "R2") (pin "2") (pinfunction "2_2") (pintype "passive"))
      (node (ref "U1") (pin "L4") (pinfunction "RBIAS_L4") (pintype "passive"))
    )
    (net (code "71") (name "Net-(U1A-RESETB)") (class "Default")
      (node (ref "R1") (pin "2") (pinfunction "2_2") (pintype "passive"))
      (node (ref "U1") (pin "K5") (pinfunction "RESETB_K5") (pintype "passive"))
    )
    (net (code "72") (name "unconnected-(U1A-AUXDAC1-PadB3)") (class "Default")
      (node (ref "U1") (pin "B3") (pinfunction "AUXDAC1_B3") (pintype "passive+no_connect"))
    )
    (net (code "73") (name "unconnected-(U1A-AUXDAC2-PadC3)") (class "Default")
      (node (ref "U1") (pin "C3") (pinfunction "AUXDAC2_C3") (pintype "passive+no_connect"))
    )
    (net (code "74") (name "unconnected-(U1A-DATA_CLK_N-PadH11)") (class "Default")
      (node (ref "U1") (pin "H11") (pinfunction "DATA_CLK_N_H11") (pintype "passive+no_connect"))
    )
    (net (code "75") (name "unconnected-(U1A-FB_CLK_N-PadG10)") (class "Default")
      (node (ref "U1") (pin "G10") (pinfunction "FB_CLK_N_G10") (pintype "passive+no_connect"))
    )
    (net (code "76") (name "unconnected-(U1A-GPO_0-PadB7)") (class "Default")
      (node (ref "U1") (pin "B7") (pinfunction "GPO_0_B7") (pintype "passive+no_connect"))
    )
    (net (code "77") (name "unconnected-(U1A-GPO_1-PadB6)") (class "Default")
      (node (ref "U1") (pin "B6") (pinfunction "GPO_1_B6") (pintype "passive+no_connect"))
    )
    (net (code "78") (name "unconnected-(U1A-GPO_2-PadB5)") (class "Default")
      (node (ref "U1") (pin "B5") (pinfunction "GPO_2_B5") (pintype "passive+no_connect"))
    )
    (net (code "79") (name "unconnected-(U1A-GPO_3-PadB4)") (class "Default")
      (node (ref "U1") (pin "B4") (pinfunction "GPO_3_B4") (pintype "passive+no_connect"))
    )
    (net (code "80") (name "unconnected-(U1A-RXB_N-PadJ1)") (class "Default")
      (node (ref "U1") (pin "J1") (pinfunction "RXB_N_J1") (pintype "passive+no_connect"))
    )
    (net (code "81") (name "unconnected-(U1A-RXB_P-PadH1)") (class "Default")
      (node (ref "U1") (pin "H1") (pinfunction "RXB_P_H1") (pintype "passive+no_connect"))
    )
    (net (code "82") (name "unconnected-(U1A-RXC_N-PadL1)") (class "Default")
      (node (ref "U1") (pin "L1") (pinfunction "RXC_N_L1") (pintype "passive+no_connect"))
    )
    (net (code "83") (name "unconnected-(U1A-RXC_P-PadK1)") (class "Default")
      (node (ref "U1") (pin "K1") (pinfunction "RXC_P_K1") (pintype "passive+no_connect"))
    )
    (net (code "84") (name "unconnected-(U1A-RX_FRAME_N-PadG7)") (class "Default")
      (node (ref "U1") (pin "G7") (pinfunction "RX_FRAME_N_G7") (pintype "passive+no_connect"))
    )
    (net (code "85") (name "unconnected-(U1A-TXB_N-PadM10)") (class "Default")
      (node (ref "U1") (pin "M10") (pinfunction "TXB_N_M10") (pintype "passive+no_connect"))
    )
    (net (code "86") (name "unconnected-(U1A-TXB_P-PadM9)") (class "Default")
      (node (ref "U1") (pin "M9") (pinfunction "TXB_P_M9") (pintype "passive+no_connect"))
    )
    (net (code "87") (name "unconnected-(U1B-NC-PadA3)") (class "Default")
      (node (ref "U1") (pin "A3") (pinfunction "NC_A3") (pintype "passive+no_connect"))
    )
    (net (code "88") (name "unconnected-(U1B-NC-PadM3)") (class "Default")
      (node (ref "U1") (pin "M3") (pinfunction "NC_M3") (pintype "passive+no_connect"))
    )
  )
)
